# PF5a_Filter1A.net
KiCad netlist of a schematic drawn in Altium Designer
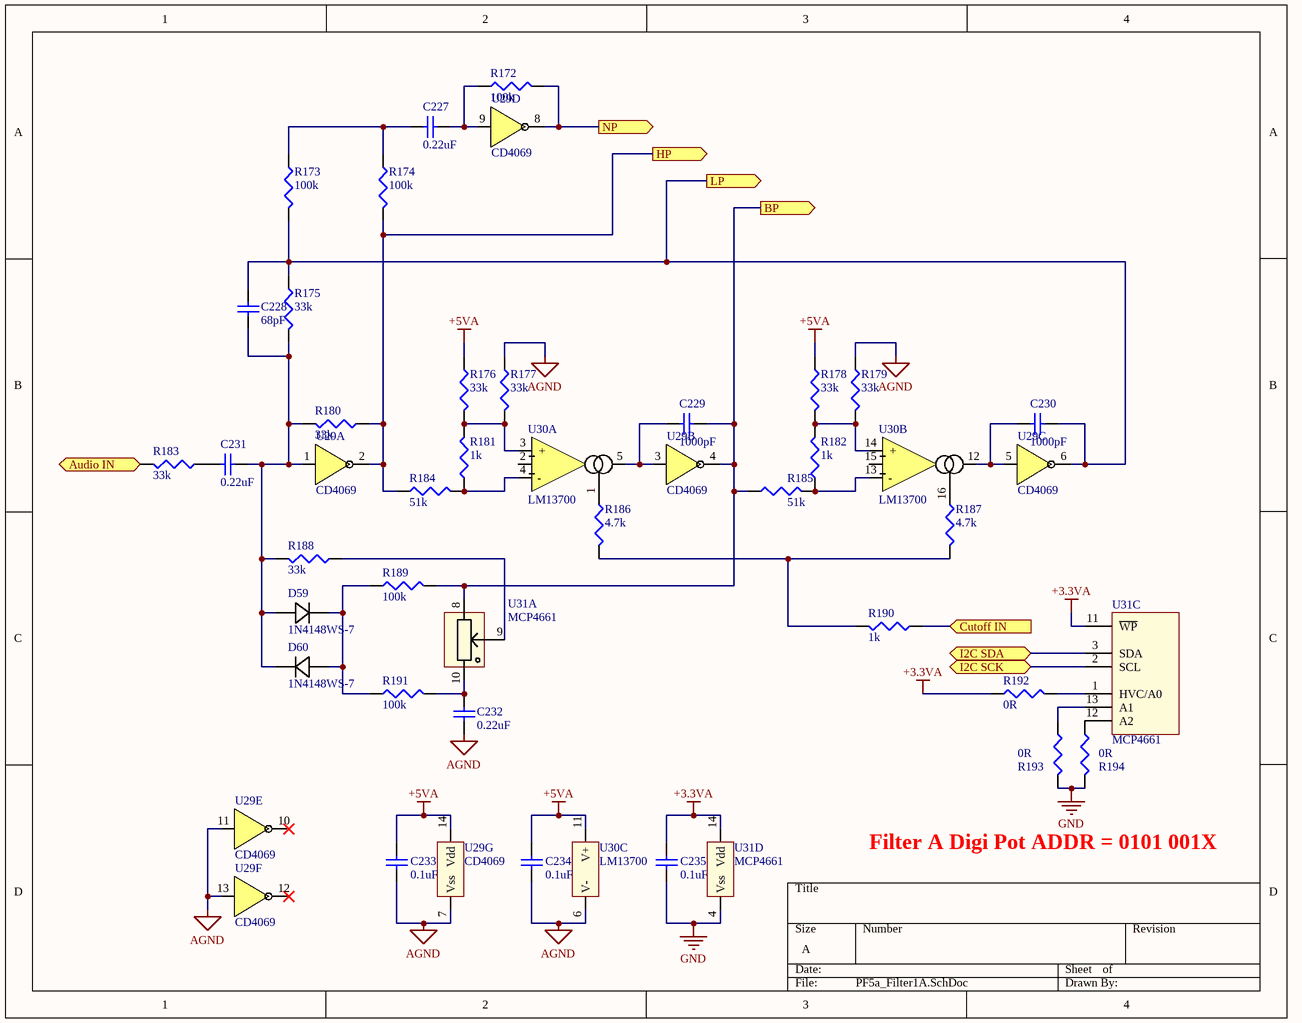
[diagram p0: PF5a_Filter1A.SchDoc]

(export (version "E")
  (design (tool "Eeschema 10.0.6"))
  (components
    (comp (ref "C227")
      (value "0.22uF")
      (footprint "CAPC1608X08")
      (description "Capacitor (Semiconductor SIM Model)")
      (libsource (lib "Michel") (part "Cap Semi"))
    )
    (comp (ref "C228")
      (value "68pF")
      (footprint "CAPC1608X08")
      (description "Capacitor (Semiconductor SIM Model)")
      (libsource (lib "Michel") (part "Cap Semi"))
    )
    (comp (ref "C229")
      (value "1000pF")
      (footprint "CAPC1608X08")
      (description "Capacitor (Semiconductor SIM Model)")
      (libsource (lib "Michel") (part "Cap Semi"))
    )
    (comp (ref "C230")
      (value "1000pF")
      (footprint "CAPC1608X08")
      (description "Capacitor (Semiconductor SIM Model)")
      (libsource (lib "Michel") (part "Cap Semi"))
    )
    (comp (ref "C231")
      (value "0.22uF")
      (footprint "CAPC1608X08")
      (description "Capacitor (Semiconductor SIM Model)")
      (libsource (lib "Michel") (part "Cap Semi"))
    )
    (comp (ref "C232")
      (value "0.22uF")
      (footprint "CAPC1608X08")
      (description "Capacitor (Semiconductor SIM Model)")
      (libsource (lib "Michel") (part "Cap Semi"))
    )
    (comp (ref "C233")
      (value "0.1uF")
      (footprint "CAPC1608X08")
      (description "Capacitor (Semiconductor SIM Model)")
      (libsource (lib "Michel") (part "Cap Semi"))
    )
    (comp (ref "C234")
      (value "0.1uF")
      (footprint "CAPC1608X08")
      (description "Capacitor (Semiconductor SIM Model)")
      (libsource (lib "Michel") (part "Cap Semi"))
    )
    (comp (ref "C235")
      (value "0.1uF")
      (footprint "CAPC1608X08")
      (description "Capacitor (Semiconductor SIM Model)")
      (libsource (lib "Michel") (part "Cap Semi"))
    )
    (comp (ref "D59")
      (value "1N4148WS-7")
      (footprint "SOD323-M")
      (description "Diode signaux faibles")
      (libsource (lib "Michel") (part "1N4148WS-7"))
    )
    (comp (ref "D60")
      (value "1N4148WS-7")
      (footprint "SOD323-M")
      (description "Diode signaux faibles")
      (libsource (lib "Michel") (part "1N4148WS-7"))
    )
    (comp (ref "R172")
      (value "100k")
      (footprint "RESC1608X05")
      (description "Resistor")
      (libsource (lib "Michel") (part "Res3"))
    )
    (comp (ref "R173")
      (value "100k")
      (footprint "RESC1608X05")
      (description "Resistor")
      (libsource (lib "Michel") (part "Res3"))
    )
    (comp (ref "R174")
      (value "100k")
      (footprint "RESC1608X05")
      (description "Resistor")
      (libsource (lib "Michel") (part "Res3"))
    )
    (comp (ref "R175")
      (value "33k")
      (footprint "RESC1608X05")
      (description "Resistor")
      (libsource (lib "Michel") (part "Res3"))
    )
    (comp (ref "R176")
      (value "33k")
      (footprint "RESC1608X05")
      (description "Resistor")
      (libsource (lib "Michel") (part "Res3"))
    )
    (comp (ref "R177")
      (value "33k")
      (footprint "RESC1608X05")
      (description "Resistor")
      (libsource (lib "Michel") (part "Res3"))
    )
    (comp (ref "R178")
      (value "33k")
      (footprint "RESC1608X05")
      (description "Resistor")
      (libsource (lib "Michel") (part "Res3"))
    )
    (comp (ref "R179")
      (value "33k")
      (footprint "RESC1608X05")
      (description "Resistor")
      (libsource (lib "Michel") (part "Res3"))
    )
    (comp (ref "R180")
      (value "33k")
      (footprint "RESC1608X05")
      (description "Resistor")
      (libsource (lib "Michel") (part "Res3"))
    )
    (comp (ref "R181")
      (value "1k")
      (footprint "RESC1608X05")
      (description "Resistor")
      (libsource (lib "Michel") (part "Res3"))
    )
    (comp (ref "R182")
      (value "1k")
      (footprint "RESC1608X05")
      (description "Resistor")
      (libsource (lib "Michel") (part "Res3"))
    )
    (comp (ref "R183")
      (value "33k")
      (footprint "RESC1608X05")
      (description "Resistor")
      (libsource (lib "Michel") (part "Res3"))
    )
    (comp (ref "R184")
      (value "51k")
      (footprint "RESC1608X05")
      (description "Resistor")
      (libsource (lib "Michel") (part "Res3"))
    )
    (comp (ref "R185")
      (value "51k")
      (footprint "RESC1608X05")
      (description "Resistor")
      (libsource (lib "Michel") (part "Res3"))
    )
    (comp (ref "R186")
      (value "4.7k")
      (footprint "RESC1608X05")
      (description "Resistor")
      (libsource (lib "Michel") (part "Res3"))
    )
    (comp (ref "R187")
      (value "4.7k")
      (footprint "RESC1608X05")
      (description "Resistor")
      (libsource (lib "Michel") (part "Res3"))
    )
    (comp (ref "R188")
      (value "33k")
      (footprint "RESC1608X05")
      (description "Resistor")
      (libsource (lib "Michel") (part "Res3"))
    )
    (comp (ref "R189")
      (value "100k")
      (footprint "RESC1608X05")
      (description "Resistor")
      (libsource (lib "Michel") (part "Res3"))
    )
    (comp (ref "R190")
      (value "1k")
      (footprint "RESC1608X05")
      (description "Resistor")
      (libsource (lib "Michel") (part "Res3"))
    )
    (comp (ref "R191")
      (value "100k")
      (footprint "RESC1608X05")
      (description "Resistor")
      (libsource (lib "Michel") (part "Res3"))
    )
    (comp (ref "R192")
      (value "0R")
      (footprint "RESC1608X05")
      (description "Resistor")
      (libsource (lib "Michel") (part "Res3"))
    )
    (comp (ref "R193")
      (value "0R")
      (footprint "RESC1608X05")
      (description "Resistor")
      (libsource (lib "Michel") (part "Res3"))
    )
    (comp (ref "R194")
      (value "0R")
      (footprint "RESC1608X05")
      (description "Resistor")
      (libsource (lib "Michel") (part "Res3"))
    )
    (comp (ref "U29")
      (value "CD4069")
      (footprint "D14-M")
      (description "Hex Inverter")
      (libsource (lib "Michel") (part "CD4069"))
    )
    (comp (ref "U30")
      (value "LM13700")
      (footprint "SO16NB")
      (description "Dual Transconductance OpAmp")
      (libsource (lib "Michel") (part "LM13700M"))
    )
    (comp (ref "U31")
      (value "MCP4661")
      (footprint "TSSOP14_MC-M")
      (description "Dual DigiPot non volatile I2C")
      (libsource (lib "Michel") (part "MCP4661"))
    )
  )
  (nets
    (net (code "1") (name "+3.3VA") (class "Default")
      (node (ref "C235") (pin "1") (pinfunction "1_1") (pintype "passive"))
      (node (ref "R192") (pin "1") (pinfunction "1_1") (pintype "passive"))
      (node (ref "U31") (pin "11") (pinfunction "~{WP}_11") (pintype "passive"))
      (node (ref "U31") (pin "14") (pinfunction "Vdd_14") (pintype "power_in"))
    )
    (net (code "2") (name "+5VA") (class "Default")
      (node (ref "C233") (pin "1") (pinfunction "1_1") (pintype "passive"))
      (node (ref "C234") (pin "1") (pinfunction "1_1") (pintype "passive"))
      (node (ref "R176") (pin "1") (pinfunction "1_1") (pintype "passive"))
      (node (ref "R178") (pin "1") (pinfunction "1_1") (pintype "passive"))
      (node (ref "U29") (pin "14") (pinfunction "Vdd_14") (pintype "power_in"))
      (node (ref "U30") (pin "11") (pinfunction "V+_11") (pintype "power_in"))
    )
    (net (code "3") (name "/Audio IN") (class "Default")
      (node (ref "R183") (pin "2") (pinfunction "2_2") (pintype "passive"))
    )
    (net (code "4") (name "/BP") (class "Default")
      (node (ref "C229") (pin "2") (pinfunction "2_2") (pintype "passive"))
      (node (ref "R185") (pin "1") (pinfunction "1_1") (pintype "passive"))
      (node (ref "R189") (pin "2") (pinfunction "2_2") (pintype "passive"))
      (node (ref "U29") (pin "4") (pinfunction "~{B}_4") (pintype "passive"))
      (node (ref "U31") (pin "8") (pinfunction "P0A_8") (pintype "passive"))
    )
    (net (code "5") (name "/Cutoff IN") (class "Default")
      (node (ref "R190") (pin "1") (pinfunction "1_1") (pintype "passive"))
    )
    (net (code "6") (name "/HP") (class "Default")
      (node (ref "R174") (pin "2") (pinfunction "2_2") (pintype "passive"))
      (node (ref "R180") (pin "1") (pinfunction "1_1") (pintype "passive"))
      (node (ref "R184") (pin "1") (pinfunction "1_1") (pintype "passive"))
      (node (ref "U29") (pin "2") (pinfunction "~{A}_2") (pintype "passive"))
    )
    (net (code "7") (name "/I2C SCK") (class "Default")
      (node (ref "U31") (pin "2") (pinfunction "SCL_2") (pintype "passive"))
    )
    (net (code "8") (name "/I2C SDA") (class "Default")
      (node (ref "U31") (pin "3") (pinfunction "SDA_3") (pintype "passive"))
    )
    (net (code "9") (name "/LP") (class "Default")
      (node (ref "C228") (pin "2") (pinfunction "2_2") (pintype "passive"))
      (node (ref "C230") (pin "2") (pinfunction "2_2") (pintype "passive"))
      (node (ref "R173") (pin "2") (pinfunction "2_2") (pintype "passive"))
      (node (ref "R175") (pin "1") (pinfunction "1_1") (pintype "passive"))
      (node (ref "U29") (pin "6") (pinfunction "~{C}_6") (pintype "passive"))
    )
    (net (code "10") (name "/NP") (class "Default")
      (node (ref "R172") (pin "2") (pinfunction "2_2") (pintype "passive"))
      (node (ref "U29") (pin "8") (pinfunction "~{D}_8") (pintype "passive"))
    )
    (net (code "11") (name "AGND") (class "Default")
      (node (ref "C232") (pin "1") (pinfunction "1_1") (pintype "passive"))
      (node (ref "C233") (pin "2") (pinfunction "2_2") (pintype "passive"))
      (node (ref "C234") (pin "2") (pinfunction "2_2") (pintype "passive"))
      (node (ref "R177") (pin "1") (pinfunction "1_1") (pintype "passive"))
      (node (ref "R179") (pin "1") (pinfunction "1_1") (pintype "passive"))
      (node (ref "U29") (pin "11") (pinfunction "E_11") (pintype "passive"))
      (node (ref "U29") (pin "13") (pinfunction "F_13") (pintype "passive"))
      (node (ref "U29") (pin "7") (pinfunction "Vss_7") (pintype "power_in"))
      (node (ref "U30") (pin "6") (pinfunction "V-_6") (pintype "power_in"))
    )
    (net (code "12") (name "GND") (class "Default")
      (node (ref "C235") (pin "2") (pinfunction "2_2") (pintype "passive"))
      (node (ref "R193") (pin "2") (pinfunction "2_2") (pintype "passive"))
      (node (ref "R194") (pin "2") (pinfunction "2_2") (pintype "passive"))
      (node (ref "U31") (pin "4") (pinfunction "Vss_4") (pintype "power_in"))
    )
    (net (code "13") (name "Net-(C227-Pad1)") (class "Default")
      (node (ref "C227") (pin "1") (pinfunction "1_1") (pintype "passive"))
      (node (ref "R173") (pin "1") (pinfunction "1_1") (pintype "passive"))
      (node (ref "R174") (pin "1") (pinfunction "1_1") (pintype "passive"))
    )
    (net (code "14") (name "Net-(C231-Pad1)") (class "Default")
      (node (ref "C231") (pin "1") (pinfunction "1_1") (pintype "passive"))
      (node (ref "R183") (pin "1") (pinfunction "1_1") (pintype "passive"))
    )
    (net (code "15") (name "Net-(D59-Pad1)") (class "Default")
      (node (ref "D59") (pin "1") (pinfunction "1_1") (pintype "passive"))
      (node (ref "D60") (pin "2") (pinfunction "2_2") (pintype "passive"))
      (node (ref "R189") (pin "1") (pinfunction "1_1") (pintype "passive"))
      (node (ref "R191") (pin "1") (pinfunction "1_1") (pintype "passive"))
    )
    (net (code "16") (name "Net-(R186-Pad2)") (class "Default")
      (node (ref "R186") (pin "2") (pinfunction "2_2") (pintype "passive"))
      (node (ref "R187") (pin "2") (pinfunction "2_2") (pintype "passive"))
      (node (ref "R190") (pin "2") (pinfunction "2_2") (pintype "passive"))
    )
    (net (code "17") (name "Net-(U29A-A)") (class "Default")
      (node (ref "C228") (pin "1") (pinfunction "1_1") (pintype "passive"))
      (node (ref "C231") (pin "2") (pinfunction "2_2") (pintype "passive"))
      (node (ref "D59") (pin "2") (pinfunction "2_2") (pintype "passive"))
      (node (ref "D60") (pin "1") (pinfunction "1_1") (pintype "passive"))
      (node (ref "R175") (pin "2") (pinfunction "2_2") (pintype "passive"))
      (node (ref "R180") (pin "2") (pinfunction "2_2") (pintype "passive"))
      (node (ref "R188") (pin "2") (pinfunction "2_2") (pintype "passive"))
      (node (ref "U29") (pin "1") (pinfunction "A_1") (pintype "passive"))
    )
    (net (code "18") (name "Net-(U29B-B)") (class "Default")
      (node (ref "C229") (pin "1") (pinfunction "1_1") (pintype "passive"))
      (node (ref "U29") (pin "3") (pinfunction "B_3") (pintype "passive"))
      (node (ref "U30") (pin "5") (pinfunction "OUT_5") (pintype "passive"))
    )
    (net (code "19") (name "Net-(U29C-C)") (class "Default")
      (node (ref "C230") (pin "1") (pinfunction "1_1") (pintype "passive"))
      (node (ref "U29") (pin "5") (pinfunction "C_5") (pintype "passive"))
      (node (ref "U30") (pin "12") (pinfunction "OUT_12") (pintype "passive"))
    )
    (net (code "20") (name "Net-(U29D-D)") (class "Default")
      (node (ref "C227") (pin "2") (pinfunction "2_2") (pintype "passive"))
      (node (ref "R172") (pin "1") (pinfunction "1_1") (pintype "passive"))
      (node (ref "U29") (pin "9") (pinfunction "D_9") (pintype "passive"))
    )
    (net (code "21") (name "Net-(U30A-+)") (class "Default")
      (node (ref "R176") (pin "2") (pinfunction "2_2") (pintype "passive"))
      (node (ref "R177") (pin "2") (pinfunction "2_2") (pintype "passive"))
      (node (ref "R181") (pin "2") (pinfunction "2_2") (pintype "passive"))
      (node (ref "U30") (pin "3") (pinfunction "+_3") (pintype "passive"))
    )
    (net (code "22") (name "Net-(U30A--)") (class "Default")
      (node (ref "R181") (pin "1") (pinfunction "1_1") (pintype "passive"))
      (node (ref "R184") (pin "2") (pinfunction "2_2") (pintype "passive"))
      (node (ref "U30") (pin "4") (pinfunction "-_4") (pintype "passive"))
    )
    (net (code "23") (name "Net-(U30A-BIAS)") (class "Default")
      (node (ref "R186") (pin "1") (pinfunction "1_1") (pintype "passive"))
      (node (ref "U30") (pin "1") (pinfunction "BIAS_1") (pintype "passive"))
    )
    (net (code "24") (name "Net-(U30B-+)") (class "Default")
      (node (ref "R178") (pin "2") (pinfunction "2_2") (pintype "passive"))
      (node (ref "R179") (pin "2") (pinfunction "2_2") (pintype "passive"))
      (node (ref "R182") (pin "2") (pinfunction "2_2") (pintype "passive"))
      (node (ref "U30") (pin "14") (pinfunction "+_14") (pintype "passive"))
    )
    (net (code "25") (name "Net-(U30B--)") (class "Default")
      (node (ref "R182") (pin "1") (pinfunction "1_1") (pintype "passive"))
      (node (ref "R185") (pin "2") (pinfunction "2_2") (pintype "passive"))
      (node (ref "U30") (pin "13") (pinfunction "-_13") (pintype "passive"))
    )
    (net (code "26") (name "Net-(U30B-BIAS)") (class "Default")
      (node (ref "R187") (pin "1") (pinfunction "1_1") (pintype "passive"))
      (node (ref "U30") (pin "16") (pinfunction "BIAS_16") (pintype "passive"))
    )
    (net (code "27") (name "Net-(U31A-P0B)") (class "Default")
      (node (ref "C232") (pin "2") (pinfunction "2_2") (pintype "passive"))
      (node (ref "R191") (pin "2") (pinfunction "2_2") (pintype "passive"))
      (node (ref "U31") (pin "10") (pinfunction "P0B_10") (pintype "passive"))
    )
    (net (code "28") (name "Net-(U31A-P0W)") (class "Default")
      (node (ref "R188") (pin "1") (pinfunction "1_1") (pintype "passive"))
      (node (ref "U31") (pin "9") (pinfunction "P0W_9") (pintype "passive"))
    )
    (net (code "29") (name "Net-(U31C-A1)") (class "Default")
      (node (ref "R193") (pin "1") (pinfunction "1_1") (pintype "passive"))
      (node (ref "U31") (pin "13") (pinfunction "A1_13") (pintype "power_in"))
    )
    (net (code "30") (name "Net-(U31C-A2)") (class "Default")
      (node (ref "R194") (pin "1") (pinfunction "1_1") (pintype "passive"))
      (node (ref "U31") (pin "12") (pinfunction "A2_12") (pintype "power_in"))
    )
    (net (code "31") (name "Net-(U31C-HVC{slash}A0)") (class "Default")
      (node (ref "R192") (pin "2") (pinfunction "2_2") (pintype "passive"))
      (node (ref "U31") (pin "1") (pinfunction "HVC/A0_1") (pintype "power_in"))
    )
    (net (code "32") (name "unconnected-(U29E-~{E}-Pad10)") (class "Default")
      (node (ref "U29") (pin "10") (pinfunction "~{E}_10") (pintype "passive+no_connect"))
    )
    (net (code "33") (name "unconnected-(U29F-~{F}-Pad12)") (class "Default")
      (node (ref "U29") (pin "12") (pinfunction "~{F}_12") (pintype "passive+no_connect"))
    )
    (net (code "34") (name "unconnected-(U30A-Diode_BIAS-Pad2)") (class "Default")
      (node (ref "U30") (pin "2") (pinfunction "Diode_BIAS_2") (pintype "passive"))
    )
    (net (code "35") (name "unconnected-(U30B-Diode_BIAS-Pad15)") (class "Default")
      (node (ref "U30") (pin "15") (pinfunction "Diode_BIAS_15") (pintype "passive"))
    )
  )
)
